# Power_Regulation_and_Protection.net
KiCad netlist of a schematic drawn in Altium Designer
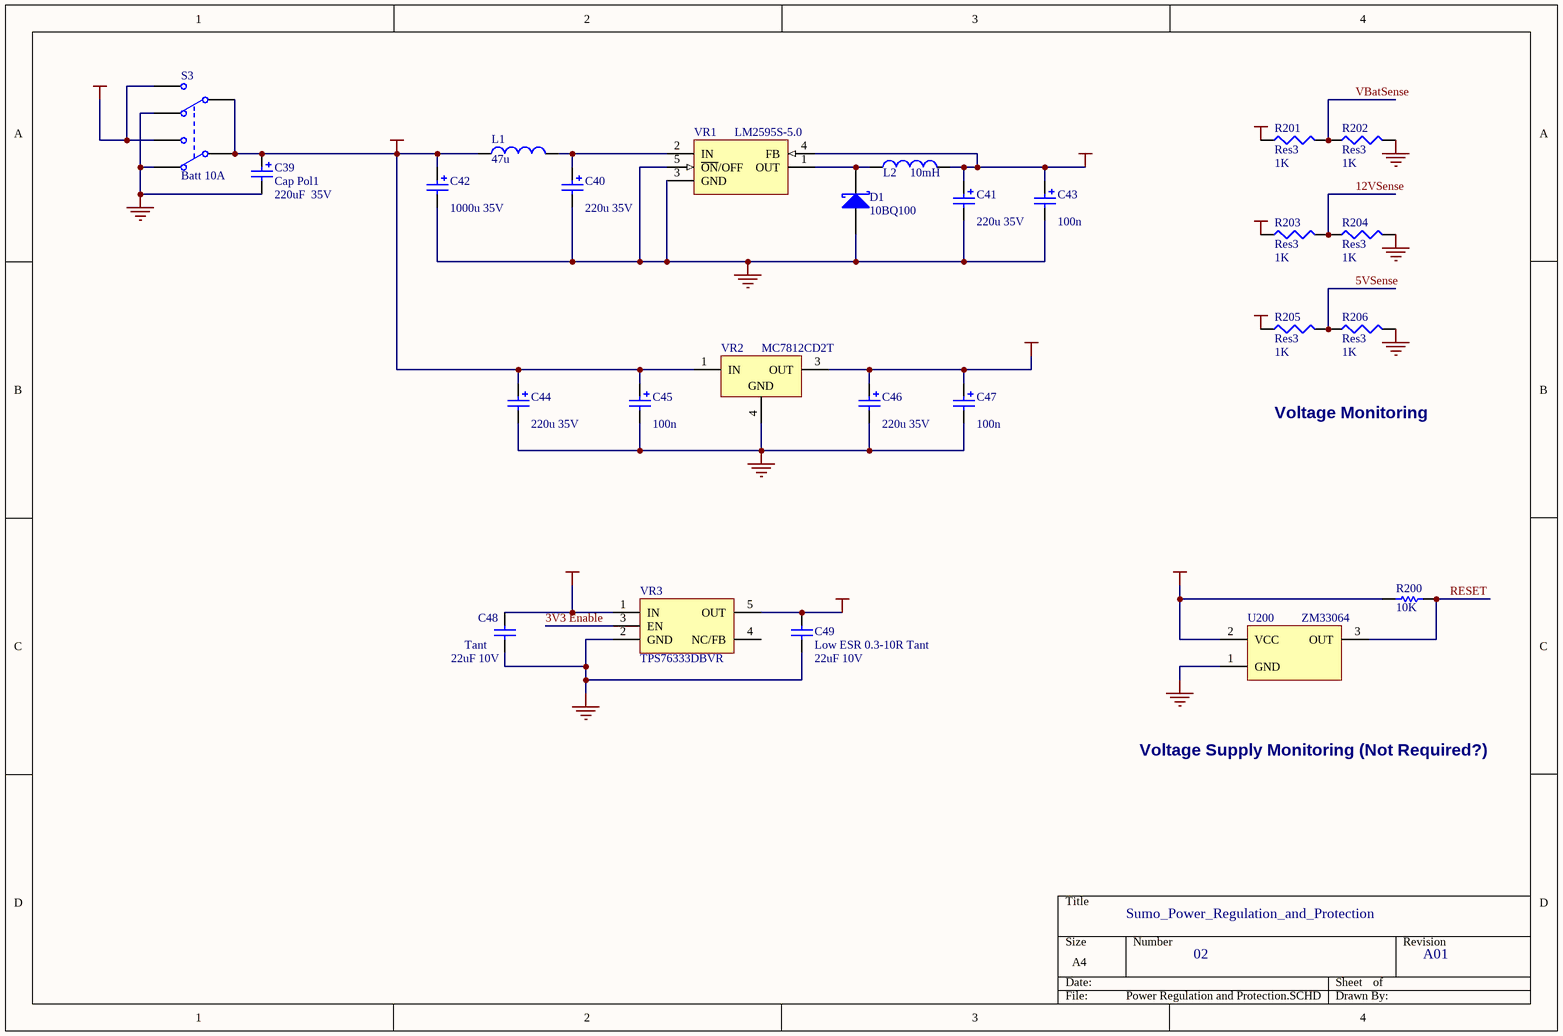
[diagram p0: Power Regulation and Protection.SCHDOC]

(export (version "E")
  (design (tool "Eeschema 10.0.6"))
  (components
    (comp (ref "C39")
      (value "Cap Pol1")
      (footprint "CAPPOL5-10X13")
      (description "Polarized Capacitor (Radial)")
      (fields (field (name "ALTIUM_VALUE") "220uF  35V") (field (name "PUBLISHER") "Altium Limited"))
      (libsource (lib "Miscellaneous Devices") (part "Cap Pol1"))
    )
    (comp (ref "C40")
      (value "220u 35V")
      (footprint "CAPPOL5-10X13")
      (description "Polarized Capacitor (Radial)")
      (fields (field (name "Comment") "Cap Pol1") (field (name "PUBLISHER") "Altium Limited"))
      (libsource (lib "Miscellaneous Devices") (part "Cap Pol1"))
    )
    (comp (ref "C41")
      (value "220u 35V")
      (footprint "CAPPOL5-10X13")
      (description "Polarized Capacitor (Radial)")
      (fields (field (name "Comment") "Cap Pol1") (field (name "PUBLISHER") "Altium Limited"))
      (libsource (lib "Miscellaneous Devices") (part "Cap Pol1"))
    )
    (comp (ref "C42")
      (value "1000u 35V")
      (footprint "CAPPOL7.5-16")
      (description "Polarized Capacitor (Radial)")
      (fields (field (name "Comment") "Cap Pol1") (field (name "PUBLISHER") "Altium Limited"))
      (libsource (lib "Miscellaneous Devices") (part "Cap Pol1"))
    )
    (comp (ref "C43")
      (value "100n")
      (footprint "CC2012-0805")
      (description "Polarized Capacitor (Surface Mount)")
      (fields (field (name "Comment") "Cap Pol3") (field (name "PUBLISHER") "Altium Limited"))
      (libsource (lib "Miscellaneous Devices") (part "Cap Pol3"))
    )
    (comp (ref "C44")
      (value "220u 35V")
      (footprint "CAPPOL5-10X13")
      (description "Polarized Capacitor (Radial)")
      (fields (field (name "Comment") "Cap Pol1") (field (name "PUBLISHER") "Altium Limited"))
      (libsource (lib "Miscellaneous Devices") (part "Cap Pol1"))
    )
    (comp (ref "C45")
      (value "100n")
      (footprint "CC2012-0805")
      (description "Polarized Capacitor (Surface Mount)")
      (fields (field (name "Comment") "Cap Pol3") (field (name "PUBLISHER") "Altium Limited"))
      (libsource (lib "Miscellaneous Devices") (part "Cap Pol3"))
    )
    (comp (ref "C46")
      (value "220u 35V")
      (footprint "CAPPOL5-10X13")
      (description "Polarized Capacitor (Radial)")
      (fields (field (name "Comment") "Cap Pol1") (field (name "PUBLISHER") "Altium Limited"))
      (libsource (lib "Miscellaneous Devices") (part "Cap Pol1"))
    )
    (comp (ref "C47")
      (value "100n")
      (footprint "CC2012-0805")
      (description "Polarized Capacitor (Surface Mount)")
      (fields (field (name "Comment") "Cap Pol3") (field (name "PUBLISHER") "Altium Limited"))
      (libsource (lib "Miscellaneous Devices") (part "Cap Pol3"))
    )
    (comp (ref "C48")
      (value "Tant")
      (footprint "CC4532-1812")
      (description "Capacitor (Semiconductor SIM Model)")
      (fields (field (name "ALTIUM_VALUE") "22uF 10V") (field (name "PUBLISHER") "Altium Limited"))
      (libsource (lib "Miscellaneous Devices") (part "Cap Semi"))
    )
    (comp (ref "C49")
      (value "Low ESR 0.3-10R Tant")
      (footprint "CC4532-1812")
      (description "Capacitor (Semiconductor SIM Model)")
      (fields (field (name "ALTIUM_VALUE") "22uF 10V") (field (name "PUBLISHER") "Altium Limited"))
      (libsource (lib "Miscellaneous Devices") (part "Cap Semi"))
    )
    (comp (ref "D1")
      (value "10BQ100")
      (footprint "SMB")
      (description "Schottky Rectifier")
      (fields (field (name "PUBLISHER") "Altium Limited"))
      (libsource (lib "IR Discrete Diode") (part "10BQ100"))
    )
    (comp (ref "L1")
      (value "47u")
      (footprint "C1005-0402")
      (description "Inductor")
      (fields (field (name "PUBLISHER") "Altium Limited"))
      (libsource (lib "Miscellaneous Devices") (part "Inductor"))
    )
    (comp (ref "L2")
      (value "10mH")
      (footprint "C1005-0402")
      (description "Inductor")
      (fields (field (name "PUBLISHER") "Altium Limited"))
      (libsource (lib "Miscellaneous Devices") (part "Inductor"))
    )
    (comp (ref "R200")
      (value "10K")
      (footprint "R2012-0805")
      (description "Resistor")
      (fields (field (name "PUBLISHER") "Altium Limited"))
      (libsource (lib "Miscellaneous Devices") (part "Res1"))
    )
    (comp (ref "R201")
      (value "Res3")
      (footprint "R2012-0805")
      (description "Resistor")
      (fields (field (name "ALTIUM_VALUE") "1K") (field (name "PUBLISHER") "Altium Limited"))
      (libsource (lib "Miscellaneous Devices") (part "Res3"))
    )
    (comp (ref "R202")
      (value "Res3")
      (footprint "R2012-0805")
      (description "Resistor")
      (fields (field (name "ALTIUM_VALUE") "1K") (field (name "PUBLISHER") "Altium Limited"))
      (libsource (lib "Miscellaneous Devices") (part "Res3"))
    )
    (comp (ref "R203")
      (value "Res3")
      (footprint "R2012-0805")
      (description "Resistor")
      (fields (field (name "ALTIUM_VALUE") "1K") (field (name "PUBLISHER") "Altium Limited"))
      (libsource (lib "Miscellaneous Devices") (part "Res3"))
    )
    (comp (ref "R204")
      (value "Res3")
      (footprint "R2012-0805")
      (description "Resistor")
      (fields (field (name "ALTIUM_VALUE") "1K") (field (name "PUBLISHER") "Altium Limited"))
      (libsource (lib "Miscellaneous Devices") (part "Res3"))
    )
    (comp (ref "R205")
      (value "Res3")
      (footprint "R2012-0805")
      (description "Resistor")
      (fields (field (name "ALTIUM_VALUE") "1K") (field (name "PUBLISHER") "Altium Limited"))
      (libsource (lib "Miscellaneous Devices") (part "Res3"))
    )
    (comp (ref "R206")
      (value "Res3")
      (footprint "R2012-0805")
      (description "Resistor")
      (fields (field (name "ALTIUM_VALUE") "1K") (field (name "PUBLISHER") "Altium Limited"))
      (libsource (lib "Miscellaneous Devices") (part "Res3"))
    )
    (comp (ref "S3")
      (value "Batt 10A")
      (footprint "SW  DPDT")
      (description "Switch")
      (fields (field (name "PUBLISHER") "Altium Limited"))
      (libsource (lib "Sumo") (part "SW DPDT"))
    )
    (comp (ref "U200")
      (value "ZM33064")
      (footprint "BCY-W3")
      (description "Generic 5V Supply Voltage Monitor")
      (libsource (lib "Schematic Library") (part "ZM33064"))
    )
    (comp (ref "VR1")
      (value "LM2595S-5.0")
      (footprint "TO-263 5 Pin SMT")
      (description "Simple Switcher Power Converter 150 kHz 1A Step Down Voltage Regulator")
      (fields (field (name "PUBLISHER") "Altium Limited"))
      (libsource (lib "NSC Power Mgt Switching Regulator") (part "LM2595S-5.0"))
    )
    (comp (ref "VR2")
      (value "MC7812CD2T")
      (footprint "936-03")
      (description "Three-Terminal Positive Voltage Regulator")
      (fields (field (name "PUBLISHER") "Altium Limited"))
      (libsource (lib "ON Semi Power Mgt Voltage Regulator") (part "MC7812CD2T"))
    )
    (comp (ref "VR3")
      (value "TPS76333DBVR")
      (footprint "SOT-23-5")
      (libsource (lib "TTCustomLibrary") (part "TPS76333DBVR"))
    )
  )
  (nets
    (net (code "1") (name "/3V3 Enable") (class "Default")
      (node (ref "VR3") (pin "3") (pinfunction "EN_3") (pintype "passive"))
    )
    (net (code "2") (name "/5VSense") (class "Default")
      (node (ref "R205") (pin "2") (pinfunction "2_2") (pintype "passive"))
      (node (ref "R206") (pin "1") (pinfunction "1_1") (pintype "passive"))
    )
    (net (code "3") (name "/12VSense") (class "Default")
      (node (ref "R203") (pin "2") (pinfunction "2_2") (pintype "passive"))
      (node (ref "R204") (pin "1") (pinfunction "1_1") (pintype "passive"))
    )
    (net (code "4") (name "/RESET") (class "Default")
      (node (ref "R200") (pin "1") (pinfunction "1_1") (pintype "passive"))
      (node (ref "U200") (pin "3") (pinfunction "OUT_3") (pintype "passive"))
    )
    (net (code "5") (name "/VBatSense") (class "Default")
      (node (ref "R201") (pin "2") (pinfunction "2_2") (pintype "passive"))
      (node (ref "R202") (pin "1") (pinfunction "1_1") (pintype "passive"))
    )
    (net (code "6") (name "3V3") (class "Default")
      (node (ref "C49") (pin "2") (pinfunction "2_2") (pintype "passive"))
      (node (ref "VR3") (pin "5") (pinfunction "OUT_5") (pintype "passive"))
    )
    (net (code "7") (name "5V") (class "Default")
      (node (ref "C41") (pin "1") (pinfunction "1_1") (pintype "passive"))
      (node (ref "C43") (pin "1") (pinfunction "1_1") (pintype "passive"))
      (node (ref "C48") (pin "2") (pinfunction "2_2") (pintype "passive"))
      (node (ref "L2") (pin "2") (pinfunction "2_2") (pintype "passive"))
      (node (ref "R200") (pin "2") (pinfunction "2_2") (pintype "passive"))
      (node (ref "R205") (pin "1") (pinfunction "1_1") (pintype "passive"))
      (node (ref "U200") (pin "2") (pinfunction "VCC_2") (pintype "passive"))
      (node (ref "VR1") (pin "4") (pinfunction "FB_4") (pintype "input"))
      (node (ref "VR3") (pin "1") (pinfunction "IN_1") (pintype "passive"))
    )
    (net (code "8") (name "12V") (class "Default")
      (node (ref "C46") (pin "1") (pinfunction "1_1") (pintype "passive"))
      (node (ref "C47") (pin "1") (pinfunction "1_1") (pintype "passive"))
      (node (ref "R203") (pin "1") (pinfunction "1_1") (pintype "passive"))
      (node (ref "VR2") (pin "3") (pinfunction "OUT_3") (pintype "power_in"))
    )
    (net (code "9") (name "GND") (class "Default")
      (node (ref "C39") (pin "2") (pinfunction "2_2") (pintype "passive"))
      (node (ref "C40") (pin "2") (pinfunction "2_2") (pintype "passive"))
      (node (ref "C41") (pin "2") (pinfunction "2_2") (pintype "passive"))
      (node (ref "C42") (pin "2") (pinfunction "2_2") (pintype "passive"))
      (node (ref "C43") (pin "2") (pinfunction "2_2") (pintype "passive"))
      (node (ref "C44") (pin "2") (pinfunction "2_2") (pintype "passive"))
      (node (ref "C45") (pin "2") (pinfunction "2_2") (pintype "passive"))
      (node (ref "C46") (pin "2") (pinfunction "2_2") (pintype "passive"))
      (node (ref "C47") (pin "2") (pinfunction "2_2") (pintype "passive"))
      (node (ref "C48") (pin "1") (pinfunction "1_1") (pintype "passive"))
      (node (ref "C49") (pin "1") (pinfunction "1_1") (pintype "passive"))
      (node (ref "D1") (pin "1") (pinfunction "A_1") (pintype "passive"))
      (node (ref "R202") (pin "2") (pinfunction "2_2") (pintype "passive"))
      (node (ref "R204") (pin "2") (pinfunction "2_2") (pintype "passive"))
      (node (ref "R206") (pin "2") (pinfunction "2_2") (pintype "passive"))
      (node (ref "S3") (pin "1") (pinfunction "NC1_1") (pintype "passive"))
      (node (ref "S3") (pin "4") (pinfunction "NC2_4") (pintype "passive"))
      (node (ref "U200") (pin "1") (pinfunction "GND_1") (pintype "passive"))
      (node (ref "VR1") (pin "3") (pinfunction "GND_3") (pintype "power_in"))
      (node (ref "VR1") (pin "5") (pinfunction "~{ON}/OFF_5") (pintype "input"))
      (node (ref "VR2") (pin "4") (pinfunction "GND_4") (pintype "power_in"))
      (node (ref "VR3") (pin "2") (pinfunction "GND_2") (pintype "passive"))
    )
    (net (code "10") (name "Net-(D1-K)") (class "Default")
      (node (ref "D1") (pin "2") (pinfunction "K_2") (pintype "passive"))
      (node (ref "L2") (pin "1") (pinfunction "1_1") (pintype "passive"))
      (node (ref "VR1") (pin "1") (pinfunction "OUT_1") (pintype "power_in"))
    )
    (net (code "11") (name "Net-(VR1-IN)") (class "Default")
      (node (ref "C40") (pin "1") (pinfunction "1_1") (pintype "passive"))
      (node (ref "L1") (pin "2") (pinfunction "2_2") (pintype "passive"))
      (node (ref "VR1") (pin "2") (pinfunction "IN_2") (pintype "power_in"))
    )
    (net (code "12") (name "VBat") (class "Default")
      (node (ref "C39") (pin "1") (pinfunction "1_1") (pintype "passive"))
      (node (ref "C42") (pin "1") (pinfunction "1_1") (pintype "passive"))
      (node (ref "C44") (pin "1") (pinfunction "1_1") (pintype "passive"))
      (node (ref "C45") (pin "1") (pinfunction "1_1") (pintype "passive"))
      (node (ref "L1") (pin "1") (pinfunction "1_1") (pintype "passive"))
      (node (ref "R201") (pin "1") (pinfunction "1_1") (pintype "passive"))
      (node (ref "S3") (pin "2") (pinfunction "COMMON1_2") (pintype "passive"))
      (node (ref "S3") (pin "5") (pinfunction "COMMON2_5") (pintype "passive"))
      (node (ref "VR2") (pin "1") (pinfunction "IN_1") (pintype "power_in"))
    )
    (net (code "13") (name "VBatIn") (class "Default")
      (node (ref "S3") (pin "3") (pinfunction "NO1_3") (pintype "passive"))
      (node (ref "S3") (pin "6") (pinfunction "NO2_6") (pintype "passive"))
    )
    (net (code "14") (name "unconnected-(VR3-NC{slash}FB-Pad4)") (class "Default")
      (node (ref "VR3") (pin "4") (pinfunction "NC/FB_4") (pintype "passive"))
    )
  )
)
